# MCU.net
KiCad netlist of a schematic drawn in Altium Designer
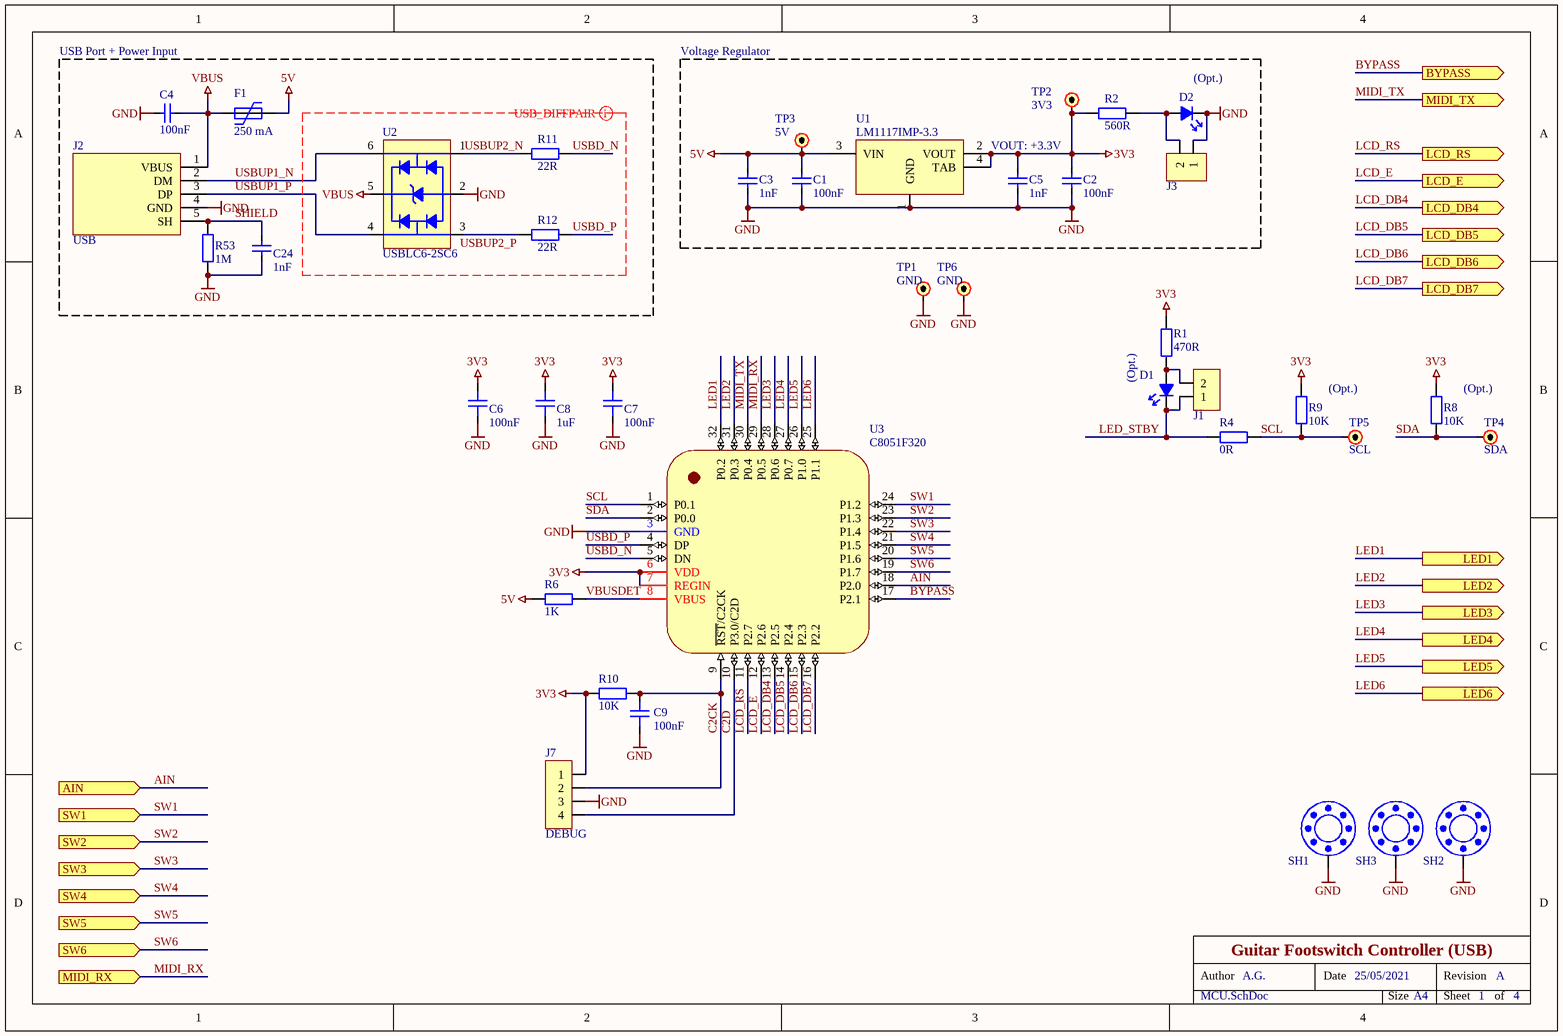
[diagram p0: MCU.SchDoc]

(export (version "E")
  (design (tool "Eeschema 10.0.6"))
  (components
    (comp (ref "C1")
      (value "100nF")
      (footprint "0805C_RF_M")
      (description "Capacitor")
      (fields (field (name "TOLERANCE") "?") (field (name "MANUFACTURER") "Generic Brand"))
      (libsource (lib "") (part "C_1"))
    )
    (comp (ref "C2")
      (value "100nF")
      (footprint "0805C_RF_M")
      (description "Capacitor")
      (fields (field (name "TOLERANCE") "?") (field (name "MANUFACTURER") "Generic Brand"))
      (libsource (lib "") (part "C_1"))
    )
    (comp (ref "C3")
      (value "1nF")
      (footprint "0805C_RF_M")
      (description "Capacitor")
      (fields (field (name "TOLERANCE") "?") (field (name "MANUFACTURER") "Generic Brand"))
      (libsource (lib "") (part "C_1"))
    )
    (comp (ref "C4")
      (value "100nF")
      (footprint "1206C_RF_M")
      (description "Capacitor")
      (fields (field (name "TOLERANCE") "?") (field (name "MANUFACTURER") "Generic Brand"))
      (libsource (lib "") (part "C_1"))
    )
    (comp (ref "C5")
      (value "1nF")
      (footprint "0805C_RF_M")
      (description "Capacitor")
      (fields (field (name "TOLERANCE") "?") (field (name "MANUFACTURER") "Generic Brand"))
      (libsource (lib "") (part "C_1"))
    )
    (comp (ref "C6")
      (value "100nF")
      (footprint "0603C_RF_M")
      (description "Capacitor")
      (fields (field (name "TOLERANCE") "?") (field (name "MANUFACTURER") "Generic Brand"))
      (libsource (lib "AG.Generic") (part "C"))
    )
    (comp (ref "C7")
      (value "100nF")
      (footprint "0603C_RF_M")
      (description "Capacitor")
      (fields (field (name "TOLERANCE") "?") (field (name "MANUFACTURER") "Generic Brand"))
      (libsource (lib "AG.Generic") (part "C"))
    )
    (comp (ref "C8")
      (value "1uF")
      (footprint "0603C_RF_M")
      (description "Capacitor")
      (fields (field (name "TOLERANCE") "?") (field (name "MANUFACTURER") "Generic Brand"))
      (libsource (lib "AG.Generic") (part "C"))
    )
    (comp (ref "C9")
      (value "100nF")
      (footprint "0603C_RF_M")
      (description "Capacitor")
      (fields (field (name "TOLERANCE") "?") (field (name "MANUFACTURER") "Generic Brand"))
      (libsource (lib "AG.Generic") (part "C"))
    )
    (comp (ref "C24")
      (value "1nF")
      (footprint "0603C_RF_M")
      (description "Capacitor")
      (fields (field (name "TOLERANCE") "?") (field (name "MANUFACTURER") "Generic Brand"))
      (libsource (lib "") (part "C_1"))
    )
    (comp (ref "D1")
      (value "LED")
      (footprint "0805LED_RF_M")
      (fields (field (name "MANUFACTURER") "Generic Brand"))
      (libsource (lib "AG.Generic") (part "LED"))
    )
    (comp (ref "D2")
      (value "LED")
      (footprint "0805LED_RF_M")
      (fields (field (name "MANUFACTURER") "Generic Brand"))
      (libsource (lib "AG.Generic") (part "LED"))
    )
    (comp (ref "F1")
      (value "250 mA")
      (footprint "BOURNS_MF-MSMF110/16-2_RF_H")
      (description "Resettable Fuse")
      (fields (field (name "MANUFACTURER") "Generic Brand"))
      (libsource (lib "AG.Generic") (part "PPTC"))
    )
    (comp (ref "J1")
      (value "LED")
      (footprint "AG.Connectors:HEADER-2.54-2P1")
      (description "Generic Pin Header 2x1")
      (libsource (lib "AG.Connectors") (part "PINHDR_2x1"))
    )
    (comp (ref "J2")
      (value "USB")
      (footprint "UJ2-BH-2-TH")
      (description "USB Type B Receptacle")
      (fields (field (name "MANUFACTURER") "Connfly"))
      (libsource (lib "AG.Connectors") (part "USBB-1J"))
    )
    (comp (ref "J3")
      (value "PINHDR_2x1")
      (footprint "AG.Connectors:HEADER-2.54-2P1")
      (description "Generic Pin Header 2x1")
      (libsource (lib "") (part "PINHDR_2x1_1"))
    )
    (comp (ref "J7")
      (value "DEBUG")
      (footprint "AG.Connectors:HEADER-2.54-4P1")
      (description "Generic Pin Header 4x1")
      (libsource (lib "AG.Connectors") (part "PINHDR_4x1"))
    )
    (comp (ref "R1")
      (value "470R")
      (footprint "0603R_RF_M")
      (description "Resistor")
      (fields (field (name "TOLERANCE") "?") (field (name "MANUFACTURER") "Generic Brand"))
      (libsource (lib "AG.Generic") (part "R"))
    )
    (comp (ref "R2")
      (value "560R")
      (footprint "0603R_RF_M")
      (description "Resistor")
      (fields (field (name "TOLERANCE") "?") (field (name "MANUFACTURER") "Generic Brand"))
      (libsource (lib "AG.Generic") (part "R"))
    )
    (comp (ref "R4")
      (value "0R")
      (footprint "0603R_RF_M")
      (description "Resistor")
      (fields (field (name "TOLERANCE") "?") (field (name "MANUFACTURER") "Generic Brand"))
      (libsource (lib "AG.Generic") (part "R"))
    )
    (comp (ref "R6")
      (value "1K")
      (footprint "0805R_RF_M")
      (description "Resistor")
      (fields (field (name "TOLERANCE") "?") (field (name "MANUFACTURER") "Generic Brand"))
      (libsource (lib "AG.Generic") (part "R"))
    )
    (comp (ref "R8")
      (value "10K")
      (footprint "0603R_RF_M")
      (description "Resistor")
      (fields (field (name "TOLERANCE") "?") (field (name "MANUFACTURER") "Generic Brand"))
      (libsource (lib "AG.Generic") (part "R"))
    )
    (comp (ref "R9")
      (value "10K")
      (footprint "0603R_RF_M")
      (description "Resistor")
      (fields (field (name "TOLERANCE") "?") (field (name "MANUFACTURER") "Generic Brand"))
      (libsource (lib "AG.Generic") (part "R"))
    )
    (comp (ref "R10")
      (value "10K")
      (footprint "0603R_RF_M")
      (description "Resistor")
      (fields (field (name "TOLERANCE") "?") (field (name "MANUFACTURER") "Generic Brand"))
      (libsource (lib "AG.Generic") (part "R"))
    )
    (comp (ref "R11")
      (value "22R")
      (footprint "0603R_RF_M")
      (description "Resistor")
      (fields (field (name "TOLERANCE") "?") (field (name "MANUFACTURER") "Generic Brand"))
      (libsource (lib "AG.Generic") (part "R"))
    )
    (comp (ref "R12")
      (value "22R")
      (footprint "0603R_RF_M")
      (description "Resistor")
      (fields (field (name "TOLERANCE") "?") (field (name "MANUFACTURER") "Generic Brand"))
      (libsource (lib "AG.Generic") (part "R"))
    )
    (comp (ref "R53")
      (value "1M")
      (footprint "0603R_RF_M")
      (description "Resistor")
      (fields (field (name "TOLERANCE") "?") (field (name "MANUFACTURER") "Generic Brand"))
      (libsource (lib "AG.Generic") (part "R"))
    )
    (comp (ref "SH1")
      (value "SH-30/57")
      (footprint "SH\\D3.0\\S5.7")
      (description "Screw Hole D3.0/5.7 T/B")
      (libsource (lib "AG.Mechanical") (part "SH-30/57"))
    )
    (comp (ref "SH2")
      (value "SH-30/57")
      (footprint "SH\\D3.0\\S5.7")
      (description "Screw Hole D3.0/5.7 T/B")
      (libsource (lib "AG.Mechanical") (part "SH-30/57"))
    )
    (comp (ref "SH3")
      (value "SH-30/57")
      (footprint "SH\\D3.0\\S5.7")
      (description "Screw Hole D3.0/5.7 T/B")
      (libsource (lib "AG.Mechanical") (part "SH-30/57"))
    )
    (comp (ref "TP1")
      (value "GND")
      (footprint "PAD_R_1.5MM")
      (description "Test Point / Pad")
      (libsource (lib "AG.Misc") (part "TP"))
    )
    (comp (ref "TP2")
      (value "3V3")
      (footprint "PAD_R_1.5MM")
      (description "Test Point / Pad")
      (libsource (lib "AG.Misc") (part "TP"))
    )
    (comp (ref "TP3")
      (value "5V")
      (footprint "PAD_R_1.5MM")
      (description "Test Point / Pad")
      (libsource (lib "AG.Misc") (part "TP"))
    )
    (comp (ref "TP4")
      (value "SDA")
      (footprint "PAD_R_1MM")
      (description "Test Point / Pad")
      (libsource (lib "AG.Misc") (part "TP"))
    )
    (comp (ref "TP5")
      (value "SCL")
      (footprint "PAD_R_1MM")
      (description "Test Point / Pad")
      (libsource (lib "AG.Misc") (part "TP"))
    )
    (comp (ref "TP6")
      (value "GND")
      (footprint "PAD_R_1.5MM")
      (description "Test Point / Pad")
      (libsource (lib "AG.Misc") (part "TP"))
    )
    (comp (ref "U1")
      (value "LM1117IMP-3.3")
      (footprint "SOT-223")
      (description "Voltage Regulator Linear 1% 800mA SOT-223")
      (fields (field (name "MANUFACTURER") "Texas Instruments") (field (name "VOUT") "+3.3V"))
      (libsource (lib "AG.IC") (part "LM1117"))
    )
    (comp (ref "U2")
      (value "USBLC6-2SC6")
      (footprint "TI_SOT-23-6")
      (description "Low Capacitance USB ESD Protection")
      (fields (field (name "MANUFACTURER") "STMicroelectronics"))
      (libsource (lib "AG.Discrete") (part "USBLC6-2SC6"))
    )
    (comp (ref "U3")
      (value "C8051F320")
      (footprint "LQFP-32")
      (description "IC MCU 8BIT 16KB FLASH 32LQFP")
      (fields
        (field (name "MANUFACTURER") "Silicon Labs")
        (field (name "MANUFACTURER PART NO") "C8051F320-GQR")
      )
      (libsource (lib "AG.MCU") (part "C8051F320"))
    )
  )
  (nets
    (net (code "1") (name "/AIN") (class "Default")
      (node (ref "U3") (pin "18") (pinfunction "P2.0_18") (pintype "bidirectional"))
    )
    (net (code "2") (name "/BYPASS") (class "Default")
      (node (ref "U3") (pin "17") (pinfunction "P2.1_17") (pintype "bidirectional"))
    )
    (net (code "3") (name "/C2CK") (class "Default")
      (node (ref "C9") (pin "2") (pinfunction "2_2") (pintype "passive"))
      (node (ref "J7") (pin "2") (pinfunction "2_2") (pintype "passive"))
      (node (ref "R10") (pin "2") (pintype "passive"))
      (node (ref "U3") (pin "9") (pinfunction "~{RST}/C2CK_9") (pintype "input"))
    )
    (net (code "4") (name "/C2D") (class "Default")
      (node (ref "J7") (pin "4") (pinfunction "4_4") (pintype "passive"))
      (node (ref "U3") (pin "10") (pinfunction "P3.0/C2D_10") (pintype "bidirectional"))
    )
    (net (code "5") (name "/LCD_DB4") (class "Default")
      (node (ref "U3") (pin "13") (pinfunction "P2.5_13") (pintype "bidirectional"))
    )
    (net (code "6") (name "/LCD_DB5") (class "Default")
      (node (ref "U3") (pin "14") (pinfunction "P2.4_14") (pintype "bidirectional"))
    )
    (net (code "7") (name "/LCD_DB6") (class "Default")
      (node (ref "U3") (pin "15") (pinfunction "P2.3_15") (pintype "bidirectional"))
    )
    (net (code "8") (name "/LCD_DB7") (class "Default")
      (node (ref "U3") (pin "16") (pinfunction "P2.2_16") (pintype "bidirectional"))
    )
    (net (code "9") (name "/LCD_E") (class "Default")
      (node (ref "U3") (pin "12") (pinfunction "P2.6_12") (pintype "bidirectional"))
    )
    (net (code "10") (name "/LCD_RS") (class "Default")
      (node (ref "U3") (pin "11") (pinfunction "P2.7_11") (pintype "bidirectional"))
    )
    (net (code "11") (name "/LED1") (class "Default")
      (node (ref "U3") (pin "32") (pinfunction "P0.2_32") (pintype "bidirectional"))
    )
    (net (code "12") (name "/LED2") (class "Default")
      (node (ref "U3") (pin "31") (pinfunction "P0.3_31") (pintype "bidirectional"))
    )
    (net (code "13") (name "/LED3") (class "Default")
      (node (ref "U3") (pin "28") (pinfunction "P0.6_28") (pintype "bidirectional"))
    )
    (net (code "14") (name "/LED4") (class "Default")
      (node (ref "U3") (pin "27") (pinfunction "P0.7_27") (pintype "bidirectional"))
    )
    (net (code "15") (name "/LED5") (class "Default")
      (node (ref "U3") (pin "26") (pinfunction "P1.0_26") (pintype "bidirectional"))
    )
    (net (code "16") (name "/LED6") (class "Default")
      (node (ref "U3") (pin "25") (pinfunction "P1.1_25") (pintype "bidirectional"))
    )
    (net (code "17") (name "/LED_STBY") (class "Default")
      (node (ref "D1") (pin "C") (pinfunction "C_C") (pintype "passive"))
      (node (ref "J1") (pin "1") (pinfunction "1_1") (pintype "passive"))
      (node (ref "R4") (pin "2") (pintype "passive"))
    )
    (net (code "18") (name "/MIDI_RX") (class "Default")
      (node (ref "U3") (pin "29") (pinfunction "P0.5_29") (pintype "bidirectional"))
    )
    (net (code "19") (name "/MIDI_TX") (class "Default")
      (node (ref "U3") (pin "30") (pinfunction "P0.4_30") (pintype "bidirectional"))
    )
    (net (code "20") (name "/SCL") (class "Default")
      (node (ref "R4") (pin "1") (pintype "passive"))
      (node (ref "R9") (pin "1") (pintype "passive"))
      (node (ref "TP5") (pin "1") (pinfunction "1_1") (pintype "passive"))
      (node (ref "U3") (pin "1") (pinfunction "P0.1_1") (pintype "bidirectional"))
    )
    (net (code "21") (name "/SDA") (class "Default")
      (node (ref "R8") (pin "1") (pintype "passive"))
      (node (ref "TP4") (pin "1") (pinfunction "1_1") (pintype "passive"))
      (node (ref "U3") (pin "2") (pinfunction "P0.0_2") (pintype "bidirectional"))
    )
    (net (code "22") (name "/SHIELD") (class "Default")
      (node (ref "C24") (pin "2") (pinfunction "2_2") (pintype "passive"))
      (node (ref "J2") (pin "5") (pinfunction "SH_5") (pintype "passive"))
      (node (ref "R53") (pin "2") (pintype "passive"))
    )
    (net (code "23") (name "/SW1") (class "Default")
      (node (ref "U3") (pin "24") (pinfunction "P1.2_24") (pintype "bidirectional"))
    )
    (net (code "24") (name "/SW2") (class "Default")
      (node (ref "U3") (pin "23") (pinfunction "P1.3_23") (pintype "bidirectional"))
    )
    (net (code "25") (name "/SW3") (class "Default")
      (node (ref "U3") (pin "22") (pinfunction "P1.4_22") (pintype "bidirectional"))
    )
    (net (code "26") (name "/SW4") (class "Default")
      (node (ref "U3") (pin "21") (pinfunction "P1.5_21") (pintype "bidirectional"))
    )
    (net (code "27") (name "/SW5") (class "Default")
      (node (ref "U3") (pin "20") (pinfunction "P1.6_20") (pintype "bidirectional"))
    )
    (net (code "28") (name "/SW6") (class "Default")
      (node (ref "U3") (pin "19") (pinfunction "P1.7_19") (pintype "bidirectional"))
    )
    (net (code "29") (name "/USBD_N") (class "Default")
      (node (ref "R11") (pin "1") (pintype "passive"))
      (node (ref "U3") (pin "5") (pinfunction "DN_5") (pintype "bidirectional"))
    )
    (net (code "30") (name "/USBD_P") (class "Default")
      (node (ref "R12") (pin "1") (pintype "passive"))
      (node (ref "U3") (pin "4") (pinfunction "DP_4") (pintype "bidirectional"))
    )
    (net (code "31") (name "/USBUP1_N") (class "Default")
      (node (ref "J2") (pin "2") (pinfunction "DM_2") (pintype "passive"))
      (node (ref "U2") (pin "6") (pinfunction "6_6") (pintype "passive"))
    )
    (net (code "32") (name "/USBUP1_P") (class "Default")
      (node (ref "J2") (pin "3") (pinfunction "DP_3") (pintype "passive"))
      (node (ref "U2") (pin "4") (pinfunction "4_4") (pintype "passive"))
    )
    (net (code "33") (name "/USBUP2_N") (class "Default")
      (node (ref "R11") (pin "2") (pintype "passive"))
      (node (ref "U2") (pin "1") (pinfunction "1_1") (pintype "passive"))
    )
    (net (code "34") (name "/USBUP2_P") (class "Default")
      (node (ref "R12") (pin "2") (pintype "passive"))
      (node (ref "U2") (pin "3") (pinfunction "3_3") (pintype "passive"))
    )
    (net (code "35") (name "/VBUSDET") (class "Default")
      (node (ref "R6") (pin "1") (pintype "passive"))
      (node (ref "U3") (pin "8") (pinfunction "VBUS_8") (pintype "power_in"))
    )
    (net (code "36") (name "3V3") (class "Default")
      (node (ref "C2") (pin "2") (pinfunction "2_2") (pintype "passive"))
      (node (ref "C5") (pin "2") (pinfunction "2_2") (pintype "passive"))
      (node (ref "C6") (pin "2") (pinfunction "2_2") (pintype "passive"))
      (node (ref "C7") (pin "2") (pinfunction "2_2") (pintype "passive"))
      (node (ref "C8") (pin "2") (pinfunction "2_2") (pintype "passive"))
      (node (ref "J7") (pin "1") (pinfunction "1_1") (pintype "passive"))
      (node (ref "R1") (pin "2") (pintype "passive"))
      (node (ref "R10") (pin "1") (pintype "passive"))
      (node (ref "R2") (pin "2") (pintype "passive"))
      (node (ref "R8") (pin "2") (pintype "passive"))
      (node (ref "R9") (pin "2") (pintype "passive"))
      (node (ref "TP2") (pin "1") (pinfunction "1_1") (pintype "passive"))
      (node (ref "U1") (pin "2") (pinfunction "VOUT_2") (pintype "passive"))
      (node (ref "U1") (pin "4") (pinfunction "TAB_4") (pintype "passive"))
      (node (ref "U3") (pin "6") (pinfunction "VDD_6") (pintype "power_in"))
      (node (ref "U3") (pin "7") (pinfunction "REGIN_7") (pintype "power_in"))
    )
    (net (code "37") (name "5V") (class "Default")
      (node (ref "C1") (pin "2") (pinfunction "2_2") (pintype "passive"))
      (node (ref "C3") (pin "2") (pinfunction "2_2") (pintype "passive"))
      (node (ref "F1") (pin "2") (pinfunction "2_2") (pintype "passive"))
      (node (ref "R6") (pin "2") (pintype "passive"))
      (node (ref "TP3") (pin "1") (pinfunction "1_1") (pintype "passive"))
      (node (ref "U1") (pin "3") (pinfunction "VIN_3") (pintype "passive"))
    )
    (net (code "38") (name "GND") (class "Default")
      (node (ref "C1") (pin "1") (pinfunction "1_1") (pintype "passive"))
      (node (ref "C2") (pin "1") (pinfunction "1_1") (pintype "passive"))
      (node (ref "C24") (pin "1") (pinfunction "1_1") (pintype "passive"))
      (node (ref "C3") (pin "1") (pinfunction "1_1") (pintype "passive"))
      (node (ref "C4") (pin "2") (pinfunction "2_2") (pintype "passive"))
      (node (ref "C5") (pin "1") (pinfunction "1_1") (pintype "passive"))
      (node (ref "C6") (pin "1") (pinfunction "1_1") (pintype "passive"))
      (node (ref "C7") (pin "1") (pinfunction "1_1") (pintype "passive"))
      (node (ref "C8") (pin "1") (pinfunction "1_1") (pintype "passive"))
      (node (ref "C9") (pin "1") (pinfunction "1_1") (pintype "passive"))
      (node (ref "D2") (pin "C") (pinfunction "C_C") (pintype "passive"))
      (node (ref "J2") (pin "4") (pinfunction "GND_4") (pintype "passive"))
      (node (ref "J3") (pin "1") (pinfunction "1_1") (pintype "passive"))
      (node (ref "J7") (pin "3") (pinfunction "3_3") (pintype "passive"))
      (node (ref "R53") (pin "1") (pintype "passive"))
      (node (ref "SH1") (pin "1") (pinfunction "1_1") (pintype "passive"))
      (node (ref "SH2") (pin "1") (pinfunction "1_1") (pintype "passive"))
      (node (ref "SH3") (pin "1") (pinfunction "1_1") (pintype "passive"))
      (node (ref "TP1") (pin "1") (pinfunction "1_1") (pintype "passive"))
      (node (ref "TP6") (pin "1") (pinfunction "1_1") (pintype "passive"))
      (node (ref "U1") (pin "1") (pinfunction "GND_1") (pintype "passive"))
      (node (ref "U2") (pin "2") (pinfunction "2_2") (pintype "passive"))
      (node (ref "U3") (pin "3") (pinfunction "GND_3") (pintype "power_in"))
    )
    (net (code "39") (name "Net-(D1-PadA)") (class "Default")
      (node (ref "D1") (pin "A") (pinfunction "A_A") (pintype "passive"))
      (node (ref "J1") (pin "2") (pinfunction "2_2") (pintype "passive"))
      (node (ref "R1") (pin "1") (pintype "passive"))
    )
    (net (code "40") (name "Net-(D2-PadA)") (class "Default")
      (node (ref "D2") (pin "A") (pinfunction "A_A") (pintype "passive"))
      (node (ref "J3") (pin "2") (pinfunction "2_2") (pintype "passive"))
      (node (ref "R2") (pin "1") (pintype "passive"))
    )
    (net (code "41") (name "VBUS") (class "Default")
      (node (ref "C4") (pin "1") (pinfunction "1_1") (pintype "passive"))
      (node (ref "F1") (pin "1") (pinfunction "1_1") (pintype "passive"))
      (node (ref "J2") (pin "1") (pinfunction "VBUS_1") (pintype "passive"))
      (node (ref "U2") (pin "5") (pinfunction "5_5") (pintype "passive"))
    )
  )
)
